# sb-sonata-usbhub.net
KiCad netlist of a schematic drawn in Altium Designer
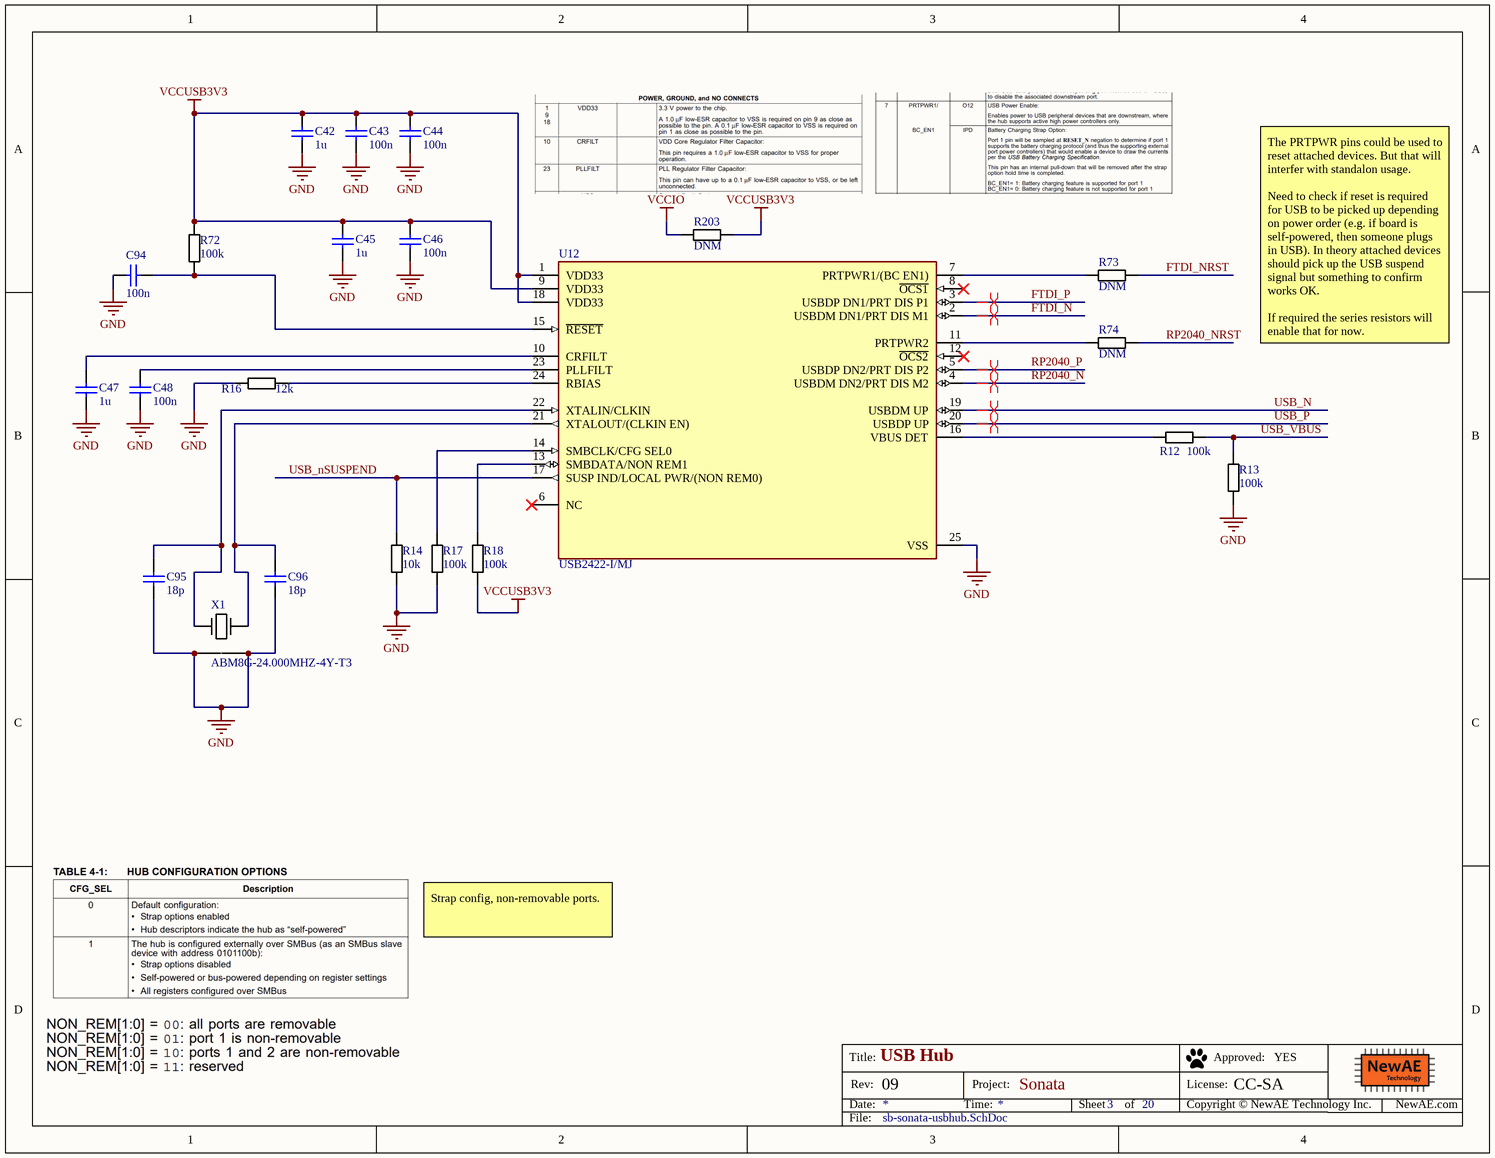
[diagram p0: sb-sonata-usbhub.SchDoc]

(export (version "E")
  (design (tool "Eeschema 10.0.6"))
  (components
    (comp (ref "C42")
      (value "1u")
      (footprint "CAPC0603_M")
      (description "1u, 0603, 50V")
      (fields (field (name "PART NUMBER") "CCHIP-1u-0603"))
      (libsource (lib "NewAE_AltiumLib") (part "CAP"))
    )
    (comp (ref "C43")
      (value "100n")
      (footprint "CAPC0402_M")
      (description "100n, 0402")
      (fields (field (name "PART NUMBER") "CCHIP-100n-0402"))
      (libsource (lib "NewAE_AltiumLib") (part "CAP"))
    )
    (comp (ref "C44")
      (value "100n")
      (footprint "CAPC0402_M")
      (description "100n, 0402")
      (fields (field (name "PART NUMBER") "CCHIP-100n-0402"))
      (libsource (lib "NewAE_AltiumLib") (part "CAP"))
    )
    (comp (ref "C45")
      (value "1u")
      (footprint "CAPC0603_M")
      (description "1u, 0603, 50V")
      (fields (field (name "PART NUMBER") "CCHIP-1u-0603"))
      (libsource (lib "NewAE_AltiumLib") (part "CAP"))
    )
    (comp (ref "C46")
      (value "100n")
      (footprint "CAPC0402_M")
      (description "100n, 0402")
      (fields (field (name "PART NUMBER") "CCHIP-100n-0402"))
      (libsource (lib "NewAE_AltiumLib") (part "CAP"))
    )
    (comp (ref "C47")
      (value "1u")
      (footprint "CAPC0603_M")
      (description "1u, 0603, 50V")
      (fields (field (name "PART NUMBER") "CCHIP-1u-0603"))
      (libsource (lib "NewAE_AltiumLib") (part "CAP"))
    )
    (comp (ref "C48")
      (value "100n")
      (footprint "CAPC0402_M")
      (description "100n, 0402")
      (fields (field (name "PART NUMBER") "CCHIP-100n-0402"))
      (libsource (lib "NewAE_AltiumLib") (part "CAP"))
    )
    (comp (ref "C94")
      (value "100n")
      (footprint "CAPC0402_M")
      (description "100n, 0402")
      (fields (field (name "PART NUMBER") "CCHIP-100n-0402"))
      (libsource (lib "NewAE_AltiumLib") (part "CAP"))
    )
    (comp (ref "C95")
      (value "18p")
      (footprint "CAPC0402_M")
      (description "18p, 0402")
      (fields (field (name "PART NUMBER") "CCHIP-18p-0402"))
      (libsource (lib "NewAE_AltiumLib") (part "CAP"))
    )
    (comp (ref "C96")
      (value "18p")
      (footprint "CAPC0402_M")
      (description "18p, 0402")
      (fields (field (name "PART NUMBER") "CCHIP-18p-0402"))
      (libsource (lib "NewAE_AltiumLib") (part "CAP"))
    )
    (comp (ref "R12")
      (value "100k")
      (footprint "RESC1005X40N")
      (description "100k res, 0402, 1%, 1/16W")
      (fields (field (name "PART NUMBER") "RCHIP-100K-0402") (field (name "TOLERANCE") "1%"))
      (libsource (lib "NewAE_AltiumLib") (part "RES-EU"))
    )
    (comp (ref "R13")
      (value "100k")
      (footprint "RESC1005X40N")
      (description "100k res, 0402, 1%, 1/16W")
      (fields (field (name "PART NUMBER") "RCHIP-100K-0402") (field (name "TOLERANCE") "1%"))
      (libsource (lib "") (part "RES-EU_1"))
    )
    (comp (ref "R14")
      (value "10k")
      (footprint "RESC1005X40N")
      (description "10k res, 0402, 1%, 1/16W")
      (fields (field (name "PART NUMBER") "RCHIP-10K-0402") (field (name "TOLERANCE") "1%"))
      (libsource (lib "") (part "RES-EU_1"))
    )
    (comp (ref "R16")
      (value "12k")
      (footprint "RESC1005X40N")
      (description "12k res, 0402, 1%, 1/16W")
      (fields (field (name "PART NUMBER") "RCHIP-12K-0402") (field (name "TOLERANCE") "1%"))
      (libsource (lib "") (part "RES-EU_3"))
    )
    (comp (ref "R17")
      (value "100k")
      (footprint "RESC1608X55N")
      (description "100k res, 0603, 1%, 1/10W")
      (fields (field (name "PART NUMBER") "RCHIP-100K-0603") (field (name "TOLERANCE") "1%"))
      (libsource (lib "") (part "RES-EU_2"))
    )
    (comp (ref "R18")
      (value "100k")
      (footprint "RESC1608X55N")
      (description "100k res, 0603, 1%, 1/10W")
      (fields (field (name "PART NUMBER") "RCHIP-100K-0603") (field (name "TOLERANCE") "1%"))
      (libsource (lib "") (part "RES-EU_2"))
    )
    (comp (ref "R72")
      (value "100k")
      (footprint "RESC1608X55N")
      (description "100k res, 0603, 1%, 1/10W")
      (fields (field (name "PART NUMBER") "RCHIP-100K-0603") (field (name "TOLERANCE") "1%"))
      (libsource (lib "") (part "RES-EU_2"))
    )
    (comp (ref "R73")
      (value "DNM")
      (footprint "RESC1005X40N")
      (fields (field (name "PART NUMBER") "RCHIP-DNM-0402"))
      (libsource (lib "NewAE_AltiumLib") (part "RES-EU"))
    )
    (comp (ref "R74")
      (value "DNM")
      (footprint "RESC1005X40N")
      (fields (field (name "PART NUMBER") "RCHIP-DNM-0402"))
      (libsource (lib "NewAE_AltiumLib") (part "RES-EU"))
    )
    (comp (ref "R203")
      (value "DNM")
      (footprint "RESC1005X40N")
      (fields (field (name "PART NUMBER") "RCHIP-DNM-0402"))
      (libsource (lib "NewAE_AltiumLib") (part "RES-EU"))
    )
    (comp (ref "U12")
      (value "USB2422-I/MJ")
      (footprint "FP-24-S4QFN-4x4B-0_5P-MFG")
      (description "IC HUB CTLR USB 2.0 24QFN")
      (fields
        (field (name "MANUFACTURER") "Microchip")
        (field (name "OCTOPART") "https://octopart.com/usb2422-i%2Fmj-microchip-29030614")
      )
      (libsource (lib "Altium Content Vault") (part "e4aea346ed290c10a3dfb05f2f32753"))
    )
    (comp (ref "X1")
      (value "ABM8G-24.000MHZ-4Y-T3")
      (footprint "ABM8G")
      (description "CRYSTAL 24.0000MHZ 10PF SMD")
      (libsource (lib "NewAE_AltiumLib") (part "XTAL_4PIN_13"))
    )
  )
  (nets
    (net (code "1") (name "/FTDI_N") (class "Default")
      (node (ref "U12") (pin "2") (pinfunction "USBDM_DN1/PRT_DIS_M1_2") (pintype "bidirectional"))
    )
    (net (code "2") (name "/FTDI_NRST") (class "Default")
      (node (ref "R73") (pin "2") (pinfunction "2_2") (pintype "passive"))
    )
    (net (code "3") (name "/FTDI_P") (class "Default")
      (node (ref "U12") (pin "3") (pinfunction "USBDP_DN1/PRT_DIS_P1_3") (pintype "bidirectional"))
    )
    (net (code "4") (name "/RP2040_N") (class "Default")
      (node (ref "U12") (pin "4") (pinfunction "USBDM_DN2/PRT_DIS_M2_4") (pintype "bidirectional"))
    )
    (net (code "5") (name "/RP2040_NRST") (class "Default")
      (node (ref "R74") (pin "2") (pinfunction "2_2") (pintype "passive"))
    )
    (net (code "6") (name "/RP2040_P") (class "Default")
      (node (ref "U12") (pin "5") (pinfunction "USBDP_DN2/PRT_DIS_P2_5") (pintype "bidirectional"))
    )
    (net (code "7") (name "/USB_N") (class "Default")
      (node (ref "U12") (pin "19") (pinfunction "USBDM_UP_19") (pintype "bidirectional"))
    )
    (net (code "8") (name "/USB_P") (class "Default")
      (node (ref "U12") (pin "20") (pinfunction "USBDP_UP_20") (pintype "bidirectional"))
    )
    (net (code "9") (name "/USB_VBUS") (class "Default")
      (node (ref "R12") (pin "2") (pinfunction "2_2") (pintype "passive"))
      (node (ref "R13") (pin "1") (pinfunction "1_1") (pintype "passive"))
    )
    (net (code "10") (name "/USB_nSUSPEND") (class "Default")
      (node (ref "R14") (pin "1") (pinfunction "1_1") (pintype "passive"))
      (node (ref "U12") (pin "17") (pinfunction "SUSP_IND/LOCAL_PWR/(NON_REM0)_17") (pintype "output"))
    )
    (net (code "11") (name "GND") (class "Default")
      (node (ref "C42") (pin "2") (pinfunction "2_2") (pintype "passive"))
      (node (ref "C43") (pin "2") (pinfunction "2_2") (pintype "passive"))
      (node (ref "C44") (pin "2") (pinfunction "2_2") (pintype "passive"))
      (node (ref "C45") (pin "2") (pinfunction "2_2") (pintype "passive"))
      (node (ref "C46") (pin "2") (pinfunction "2_2") (pintype "passive"))
      (node (ref "C47") (pin "2") (pinfunction "2_2") (pintype "passive"))
      (node (ref "C48") (pin "2") (pinfunction "2_2") (pintype "passive"))
      (node (ref "C94") (pin "2") (pinfunction "2_2") (pintype "passive"))
      (node (ref "C95") (pin "2") (pinfunction "2_2") (pintype "passive"))
      (node (ref "C96") (pin "2") (pinfunction "2_2") (pintype "passive"))
      (node (ref "R13") (pin "2") (pinfunction "2_2") (pintype "passive"))
      (node (ref "R14") (pin "2") (pinfunction "2_2") (pintype "passive"))
      (node (ref "R16") (pin "2") (pinfunction "2_2") (pintype "passive"))
      (node (ref "R17") (pin "1") (pinfunction "1_1") (pintype "passive"))
      (node (ref "U12") (pin "25") (pinfunction "VSS_25") (pintype "power_in"))
      (node (ref "X1") (pin "2") (pinfunction "GND_2") (pintype "power_in"))
      (node (ref "X1") (pin "4") (pinfunction "GND_4") (pintype "power_in"))
    )
    (net (code "12") (name "Net-(U12-CRFILT)") (class "Default")
      (node (ref "C47") (pin "1") (pinfunction "1_1") (pintype "passive"))
      (node (ref "U12") (pin "10") (pinfunction "CRFILT_10") (pintype "passive"))
    )
    (net (code "13") (name "Net-(U12-PLLFILT)") (class "Default")
      (node (ref "C48") (pin "1") (pinfunction "1_1") (pintype "passive"))
      (node (ref "U12") (pin "23") (pinfunction "PLLFILT_23") (pintype "passive"))
    )
    (net (code "14") (name "Net-(U12-PRTPWR1{slash}(BC_EN1))") (class "Default")
      (node (ref "R73") (pin "1") (pinfunction "1_1") (pintype "passive"))
      (node (ref "U12") (pin "7") (pinfunction "PRTPWR1/(BC_EN1)_7") (pintype "power_in"))
    )
    (net (code "15") (name "Net-(U12-PRTPWR2)") (class "Default")
      (node (ref "R74") (pin "1") (pinfunction "1_1") (pintype "passive"))
      (node (ref "U12") (pin "11") (pinfunction "PRTPWR2_11") (pintype "power_in"))
    )
    (net (code "16") (name "Net-(U12-RBIAS)") (class "Default")
      (node (ref "R16") (pin "1") (pinfunction "1_1") (pintype "passive"))
      (node (ref "U12") (pin "24") (pinfunction "RBIAS_24") (pintype "passive"))
    )
    (net (code "17") (name "Net-(U12-SMBCLK{slash}CFG_SEL0)") (class "Default")
      (node (ref "R17") (pin "2") (pinfunction "2_2") (pintype "passive"))
      (node (ref "U12") (pin "14") (pinfunction "SMBCLK/CFG_SEL0_14") (pintype "input"))
    )
    (net (code "18") (name "Net-(U12-SMBDATA{slash}NON_REM1)") (class "Default")
      (node (ref "R18") (pin "2") (pinfunction "2_2") (pintype "passive"))
      (node (ref "U12") (pin "13") (pinfunction "SMBDATA/NON_REM1_13") (pintype "bidirectional"))
    )
    (net (code "19") (name "Net-(U12-VBUS_DET)") (class "Default")
      (node (ref "R12") (pin "1") (pinfunction "1_1") (pintype "passive"))
      (node (ref "U12") (pin "16") (pinfunction "VBUS_DET_16") (pintype "power_in"))
    )
    (net (code "20") (name "Net-(U12-XTALIN{slash}CLKIN)") (class "Default")
      (node (ref "C95") (pin "1") (pinfunction "1_1") (pintype "passive"))
      (node (ref "U12") (pin "22") (pinfunction "XTALIN/CLKIN_22") (pintype "input"))
      (node (ref "X1") (pin "3") (pinfunction "OUT_3") (pintype "passive"))
    )
    (net (code "21") (name "Net-(U12-XTALOUT{slash}(CLKIN_EN))") (class "Default")
      (node (ref "C96") (pin "1") (pinfunction "1_1") (pintype "passive"))
      (node (ref "U12") (pin "21") (pinfunction "XTALOUT/(CLKIN_EN)_21") (pintype "output"))
      (node (ref "X1") (pin "1") (pinfunction "IN_1") (pintype "passive"))
    )
    (net (code "22") (name "Net-(U12-~{RESET})") (class "Default")
      (node (ref "C94") (pin "1") (pinfunction "1_1") (pintype "passive"))
      (node (ref "R72") (pin "1") (pinfunction "1_1") (pintype "passive"))
      (node (ref "U12") (pin "15") (pinfunction "~{RESET}_15") (pintype "input"))
    )
    (net (code "23") (name "VCCIO") (class "Default")
      (node (ref "R203") (pin "1") (pinfunction "1_1") (pintype "passive"))
    )
    (net (code "24") (name "VCCUSB3V3") (class "Default")
      (node (ref "C42") (pin "1") (pinfunction "1_1") (pintype "passive"))
      (node (ref "C43") (pin "1") (pinfunction "1_1") (pintype "passive"))
      (node (ref "C44") (pin "1") (pinfunction "1_1") (pintype "passive"))
      (node (ref "C45") (pin "1") (pinfunction "1_1") (pintype "passive"))
      (node (ref "C46") (pin "1") (pinfunction "1_1") (pintype "passive"))
      (node (ref "R18") (pin "1") (pinfunction "1_1") (pintype "passive"))
      (node (ref "R203") (pin "2") (pinfunction "2_2") (pintype "passive"))
      (node (ref "R72") (pin "2") (pinfunction "2_2") (pintype "passive"))
      (node (ref "U12") (pin "1") (pinfunction "VDD33_1") (pintype "power_in"))
      (node (ref "U12") (pin "18") (pinfunction "VDD33_18") (pintype "power_in"))
      (node (ref "U12") (pin "9") (pinfunction "VDD33_9") (pintype "power_in"))
    )
    (net (code "25") (name "unconnected-(U12-NC-Pad6)") (class "Default")
      (node (ref "U12") (pin "6") (pinfunction "NC_6") (pintype "passive+no_connect"))
    )
    (net (code "26") (name "unconnected-(U12-~{OCS1}-Pad8)") (class "Default")
      (node (ref "U12") (pin "8") (pinfunction "~{OCS1}_8") (pintype "input+no_connect"))
    )
    (net (code "27") (name "unconnected-(U12-~{OCS2}-Pad12)") (class "Default")
      (node (ref "U12") (pin "12") (pinfunction "~{OCS2}_12") (pintype "input+no_connect"))
    )
  )
)
